# inkubator.net
KiCad netlist of a schematic drawn in EAGLE
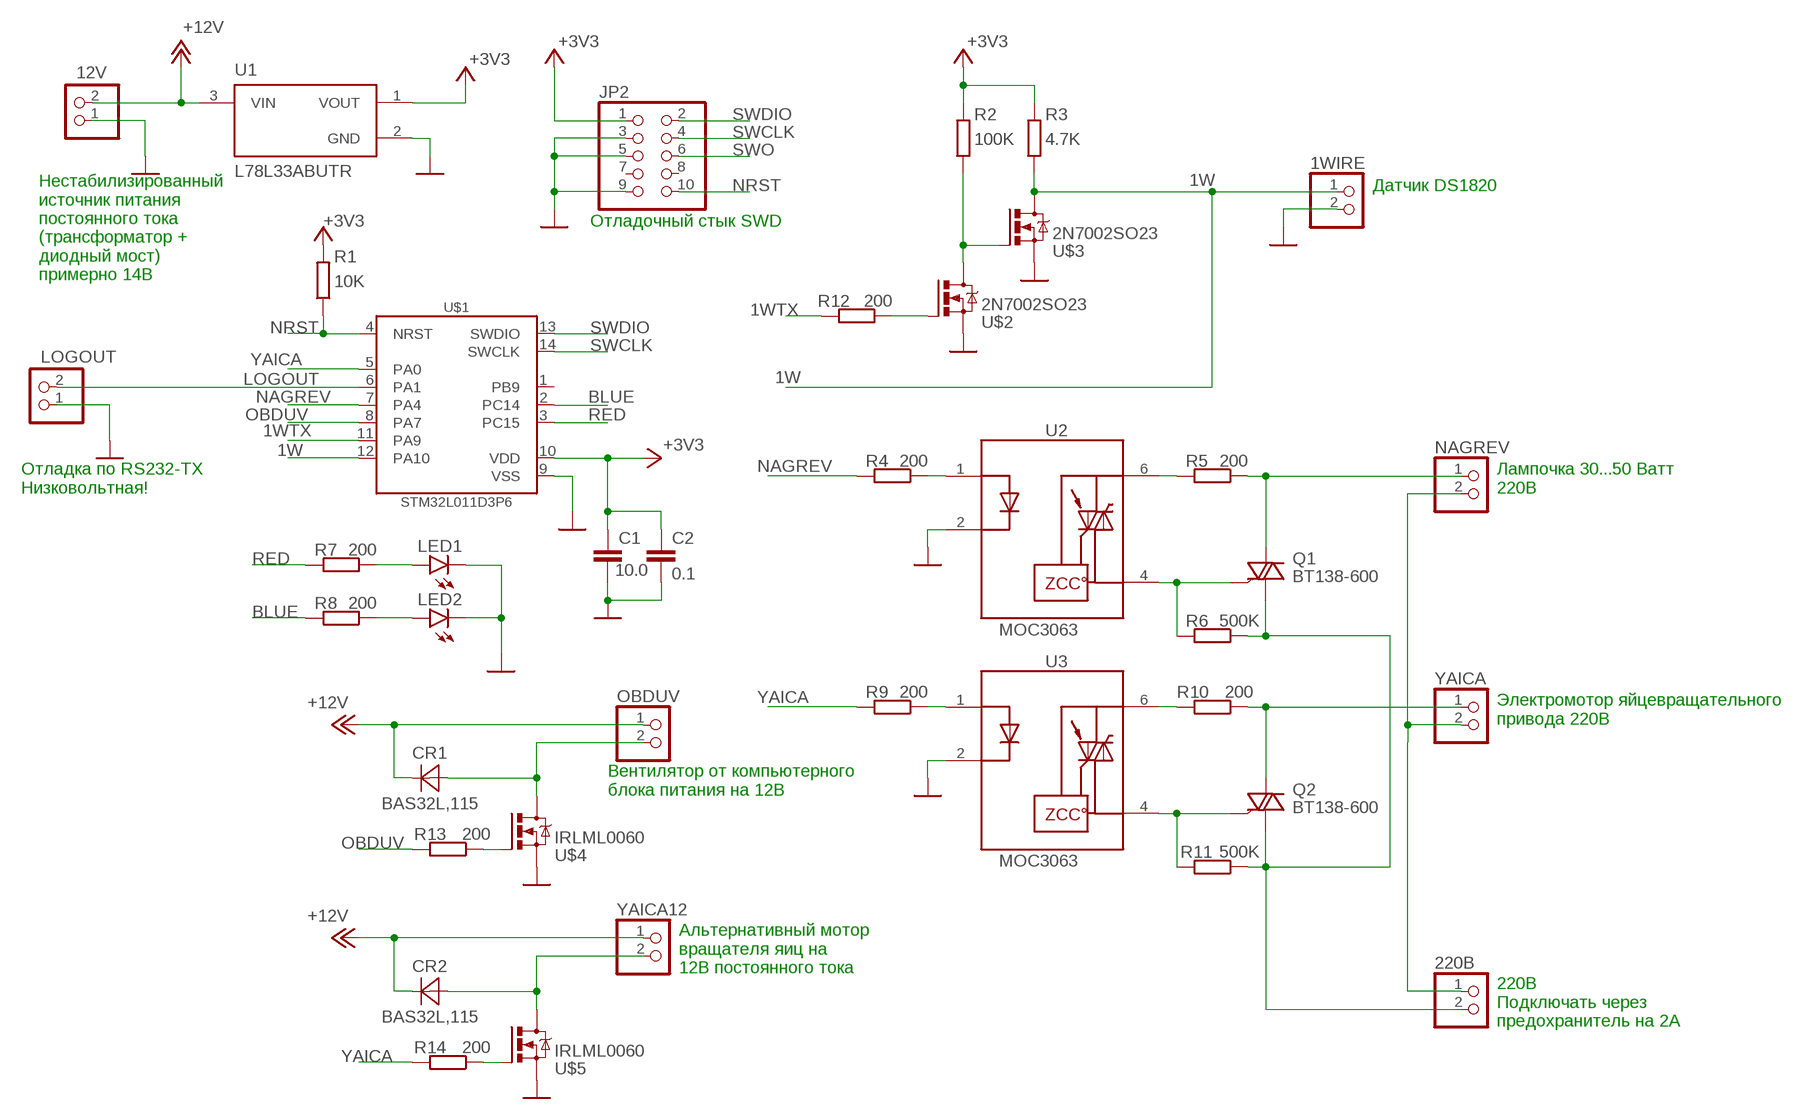
[diagram p0: schematic, sheet 1]

(export (version "E")
  (design (tool "Eeschema 10.0.6"))
  (components
    (comp (ref "1WIRE")
      (value "PINHD-1X2")
      (footprint "eagle-import:1X02")
      (libsource (lib "eagle-import") (part "PINHD-1X2"))
    )
    (comp (ref "12V")
      (value "PINHD-1X2")
      (footprint "eagle-import:1X02")
      (libsource (lib "eagle-import") (part "PINHD-1X2"))
    )
    (comp (ref "220В")
      (value "PINHD-1X2")
      (footprint "eagle-import:1X02")
      (libsource (lib "eagle-import") (part "PINHD-1X2"))
    )
    (comp (ref "C1")
      (value "10.0")
      (footprint "eagle-import:C1206")
      (libsource (lib "eagle-import") (part "C-EUC1206"))
    )
    (comp (ref "C2")
      (value "0.1")
      (footprint "eagle-import:C1206")
      (libsource (lib "eagle-import") (part "C-EUC1206"))
    )
    (comp (ref "CR1")
      (value "BAS32L,115")
      (footprint "eagle-import:SOD80C")
      (fields (field (name "MF") "Nexperia USA"))
      (libsource (lib "eagle-import") (part "BAS32L,115"))
    )
    (comp (ref "CR2")
      (value "BAS32L,115")
      (footprint "eagle-import:SOD80C")
      (fields (field (name "MF") "Nexperia USA"))
      (libsource (lib "eagle-import") (part "BAS32L,115"))
    )
    (comp (ref "JP2")
      (value "PINHD-2X5")
      (footprint "eagle-import:2X05")
      (libsource (lib "eagle-import") (part "PINHD-2X5"))
    )
    (comp (ref "LED1")
      (value "LED10MM")
      (footprint "eagle-import:LED10MM")
      (libsource (lib "eagle-import") (part "LED10MM"))
    )
    (comp (ref "LED2")
      (value "LED10MM")
      (footprint "eagle-import:LED10MM")
      (libsource (lib "eagle-import") (part "LED10MM"))
    )
    (comp (ref "LOGOUT")
      (value "PINHD-1X2")
      (footprint "eagle-import:1X02")
      (libsource (lib "eagle-import") (part "PINHD-1X2"))
    )
    (comp (ref "NAGREV")
      (value "PINHD-1X2")
      (footprint "eagle-import:1X02")
      (libsource (lib "eagle-import") (part "PINHD-1X2"))
    )
    (comp (ref "OBDUV")
      (value "PINHD-1X2")
      (footprint "eagle-import:1X02")
      (libsource (lib "eagle-import") (part "PINHD-1X2"))
    )
    (comp (ref "Q1")
      (value "BT138-600")
      (footprint "eagle-import:DPAK")
      (fields (field (name "MF") "STMicroelectronics") (field (name "MP") "T810-600B-TR"))
      (libsource (lib "eagle-import") (part "T810-600B-TR"))
    )
    (comp (ref "Q2")
      (value "BT138-600")
      (footprint "eagle-import:DPAK")
      (fields (field (name "MF") "STMicroelectronics") (field (name "MP") "T810-600B-TR"))
      (libsource (lib "eagle-import") (part "T810-600B-TR"))
    )
    (comp (ref "R1")
      (value "10K")
      (footprint "eagle-import:R0603")
      (libsource (lib "eagle-import") (part "R-EU_R0603"))
    )
    (comp (ref "R2")
      (value "100K")
      (footprint "eagle-import:R0603")
      (libsource (lib "eagle-import") (part "R-EU_R0603"))
    )
    (comp (ref "R3")
      (value "4.7K")
      (footprint "eagle-import:R0603")
      (libsource (lib "eagle-import") (part "R-EU_R0603"))
    )
    (comp (ref "R4")
      (value "200")
      (footprint "eagle-import:R0603")
      (libsource (lib "eagle-import") (part "R-EU_R0603"))
    )
    (comp (ref "R5")
      (value "200")
      (footprint "eagle-import:R1206")
      (libsource (lib "eagle-import") (part "R-EU_R1206"))
    )
    (comp (ref "R6")
      (value "500K")
      (footprint "eagle-import:R1206")
      (libsource (lib "eagle-import") (part "R-EU_R1206"))
    )
    (comp (ref "R7")
      (value "200")
      (footprint "eagle-import:R0603")
      (libsource (lib "eagle-import") (part "R-EU_R0603"))
    )
    (comp (ref "R8")
      (value "200")
      (footprint "eagle-import:R0603")
      (libsource (lib "eagle-import") (part "R-EU_R0603"))
    )
    (comp (ref "R9")
      (value "200")
      (footprint "eagle-import:R0603")
      (libsource (lib "eagle-import") (part "R-EU_R0603"))
    )
    (comp (ref "R10")
      (value "200")
      (footprint "eagle-import:R1206")
      (libsource (lib "eagle-import") (part "R-EU_R1206"))
    )
    (comp (ref "R11")
      (value "500K")
      (footprint "eagle-import:R1206")
      (libsource (lib "eagle-import") (part "R-EU_R1206"))
    )
    (comp (ref "R12")
      (value "200")
      (footprint "eagle-import:R0603")
      (libsource (lib "eagle-import") (part "R-EU_R0603"))
    )
    (comp (ref "R13")
      (value "200")
      (footprint "eagle-import:R0603")
      (libsource (lib "eagle-import") (part "R-EU_R0603"))
    )
    (comp (ref "R14")
      (value "200")
      (footprint "eagle-import:R0603")
      (libsource (lib "eagle-import") (part "R-EU_R0603"))
    )
    (comp (ref "U$1")
      (value "STM32L011D3P6")
      (footprint "eagle-import:SOP65P640X120-14N")
      (libsource (lib "eagle-import") (part "STM32L011D3P6"))
    )
    (comp (ref "U$2")
      (value "2N7002SO23")
      (footprint "eagle-import:SOT23")
      (libsource (lib "eagle-import") (part "2N7002SO23"))
    )
    (comp (ref "U$3")
      (value "2N7002SO23")
      (footprint "eagle-import:SOT23")
      (libsource (lib "eagle-import") (part "2N7002SO23"))
    )
    (comp (ref "U$4")
      (value "IRLML0060")
      (footprint "eagle-import:SOT23")
      (libsource (lib "eagle-import") (part "2N7002SO23"))
    )
    (comp (ref "U$5")
      (value "IRLML0060")
      (footprint "eagle-import:SOT23")
      (libsource (lib "eagle-import") (part "2N7002SO23"))
    )
    (comp (ref "U1")
      (value "L78L33ABUTR")
      (footprint "eagle-import:VREG_L78L12ABUTR")
      (fields (field (name "MF") "STMicroelectronics") (field (name "MP") "L78L12ABUTR"))
      (libsource (lib "eagle-import") (part "L78L12ABUTR"))
    )
    (comp (ref "U2")
      (value "MOC3063")
      (footprint "eagle-import:SOIC254P1030X460-6N")
      (fields (field (name "MF") "Vishay Semiconductor") (field (name "MP") "VO3062-X017T"))
      (libsource (lib "eagle-import") (part "VO3062-X017T"))
    )
    (comp (ref "U3")
      (value "MOC3063")
      (footprint "eagle-import:SOIC254P1030X460-6N")
      (fields (field (name "MF") "Vishay Semiconductor") (field (name "MP") "VO3062-X017T"))
      (libsource (lib "eagle-import") (part "VO3062-X017T"))
    )
    (comp (ref "YAICA")
      (value "PINHD-1X2")
      (footprint "eagle-import:1X02")
      (libsource (lib "eagle-import") (part "PINHD-1X2"))
    )
    (comp (ref "YAICA12")
      (value "PINHD-1X2")
      (footprint "eagle-import:1X02")
      (libsource (lib "eagle-import") (part "PINHD-1X2"))
    )
  )
  (nets
    (net (code "1") (name "+3V3") (class "Default")
      (node (ref "C1") (pin "1") (pinfunction "1_1") (pintype "passive"))
      (node (ref "C2") (pin "1") (pinfunction "1_1") (pintype "passive"))
      (node (ref "JP2") (pin "1") (pinfunction "1_1") (pintype "passive"))
      (node (ref "R1") (pin "2") (pinfunction "2_2") (pintype "passive"))
      (node (ref "R2") (pin "2") (pinfunction "2_2") (pintype "passive"))
      (node (ref "R3") (pin "2") (pinfunction "2_2") (pintype "passive"))
      (node (ref "U$1") (pin "10") (pinfunction "VDD_10") (pintype "power_in"))
      (node (ref "U1") (pin "1") (pinfunction "VOUT_1") (pintype "output"))
    )
    (net (code "2") (name "+12V") (class "Default")
      (node (ref "12V") (pin "2") (pinfunction "2_2") (pintype "passive"))
      (node (ref "CR1") (pin "1") (pinfunction "CATHODE_1") (pintype "passive"))
      (node (ref "CR2") (pin "1") (pinfunction "CATHODE_1") (pintype "passive"))
      (node (ref "OBDUV") (pin "1") (pinfunction "1_1") (pintype "passive"))
      (node (ref "U1") (pin "3") (pinfunction "VIN_3") (pintype "input"))
      (node (ref "YAICA12") (pin "1") (pinfunction "1_1") (pintype "passive"))
    )
    (net (code "3") (name "/1W") (class "Default")
      (node (ref "1WIRE") (pin "1") (pinfunction "1_1") (pintype "passive"))
      (node (ref "R3") (pin "1") (pinfunction "1_1") (pintype "passive"))
      (node (ref "U$1") (pin "12") (pinfunction "PA10_12") (pintype "bidirectional"))
      (node (ref "U$3") (pin "3") (pinfunction "D_3") (pintype "bidirectional"))
    )
    (net (code "4") (name "/1WTX") (class "Default")
      (node (ref "R12") (pin "2") (pinfunction "2_2") (pintype "passive"))
      (node (ref "U$1") (pin "11") (pinfunction "PA9_11") (pintype "bidirectional"))
    )
    (net (code "5") (name "/BLUE") (class "Default")
      (node (ref "R8") (pin "2") (pinfunction "2_2") (pintype "passive"))
      (node (ref "U$1") (pin "2") (pinfunction "PC14_2") (pintype "bidirectional"))
    )
    (net (code "6") (name "/LOGOUT") (class "Default")
      (node (ref "LOGOUT") (pin "2") (pinfunction "2_2") (pintype "passive"))
      (node (ref "U$1") (pin "6") (pinfunction "PA1_6") (pintype "bidirectional"))
    )
    (net (code "7") (name "/NAGREV") (class "Default")
      (node (ref "R4") (pin "2") (pinfunction "2_2") (pintype "passive"))
      (node (ref "U$1") (pin "7") (pinfunction "PA4_7") (pintype "bidirectional"))
    )
    (net (code "8") (name "/NRST") (class "Default")
      (node (ref "JP2") (pin "10") (pinfunction "10_10") (pintype "passive"))
      (node (ref "R1") (pin "1") (pinfunction "1_1") (pintype "passive"))
      (node (ref "U$1") (pin "4") (pinfunction "NRST_4") (pintype "input"))
    )
    (net (code "9") (name "/OBDUV") (class "Default")
      (node (ref "R13") (pin "2") (pinfunction "2_2") (pintype "passive"))
      (node (ref "U$1") (pin "8") (pinfunction "PA7_8") (pintype "bidirectional"))
    )
    (net (code "10") (name "/RED") (class "Default")
      (node (ref "R7") (pin "2") (pinfunction "2_2") (pintype "passive"))
      (node (ref "U$1") (pin "3") (pinfunction "PC15_3") (pintype "bidirectional"))
    )
    (net (code "11") (name "/SWCLK") (class "Default")
      (node (ref "JP2") (pin "4") (pinfunction "4_4") (pintype "passive"))
      (node (ref "U$1") (pin "14") (pinfunction "SWCLK_14") (pintype "bidirectional"))
    )
    (net (code "12") (name "/SWDIO") (class "Default")
      (node (ref "JP2") (pin "2") (pinfunction "2_2") (pintype "passive"))
      (node (ref "U$1") (pin "13") (pinfunction "SWDIO_13") (pintype "bidirectional"))
    )
    (net (code "13") (name "/SWO") (class "Default")
      (node (ref "JP2") (pin "6") (pinfunction "6_6") (pintype "passive"))
    )
    (net (code "14") (name "/YAICA") (class "Default")
      (node (ref "R14") (pin "2") (pinfunction "2_2") (pintype "passive"))
      (node (ref "R9") (pin "2") (pinfunction "2_2") (pintype "passive"))
      (node (ref "U$1") (pin "5") (pinfunction "PA0_5") (pintype "bidirectional"))
    )
    (net (code "15") (name "GND") (class "Default")
      (node (ref "12V") (pin "1") (pinfunction "1_1") (pintype "passive"))
      (node (ref "1WIRE") (pin "2") (pinfunction "2_2") (pintype "passive"))
      (node (ref "C1") (pin "2") (pinfunction "2_2") (pintype "passive"))
      (node (ref "C2") (pin "2") (pinfunction "2_2") (pintype "passive"))
      (node (ref "JP2") (pin "3") (pinfunction "3_3") (pintype "passive"))
      (node (ref "JP2") (pin "5") (pinfunction "5_5") (pintype "passive"))
      (node (ref "JP2") (pin "9") (pinfunction "9_9") (pintype "passive"))
      (node (ref "LED1") (pin "K") (pinfunction "C_K") (pintype "passive"))
      (node (ref "LED2") (pin "K") (pinfunction "C_K") (pintype "passive"))
      (node (ref "LOGOUT") (pin "1") (pinfunction "1_1") (pintype "passive"))
      (node (ref "U$1") (pin "9") (pinfunction "VSS_9") (pintype "power_in"))
      (node (ref "U$2") (pin "2") (pinfunction "S_2") (pintype "bidirectional"))
      (node (ref "U$3") (pin "2") (pinfunction "S_2") (pintype "bidirectional"))
      (node (ref "U$4") (pin "2") (pinfunction "S_2") (pintype "bidirectional"))
      (node (ref "U$5") (pin "2") (pinfunction "S_2") (pintype "bidirectional"))
      (node (ref "U1") (pin "2") (pinfunction "GND_2") (pintype "power_in"))
      (node (ref "U2") (pin "2") (pinfunction "C_2") (pintype "passive"))
      (node (ref "U3") (pin "2") (pinfunction "C_2") (pintype "passive"))
    )
    (net (code "16") (name "Net-(220В-Pad1)") (class "Default")
      (node (ref "220В") (pin "1") (pinfunction "1_1") (pintype "passive"))
      (node (ref "NAGREV") (pin "2") (pinfunction "2_2") (pintype "passive"))
      (node (ref "YAICA") (pin "2") (pinfunction "2_2") (pintype "passive"))
    )
    (net (code "17") (name "Net-(CR1-ANODE)") (class "Default")
      (node (ref "CR1") (pin "2") (pinfunction "ANODE_2") (pintype "passive"))
      (node (ref "OBDUV") (pin "2") (pinfunction "2_2") (pintype "passive"))
      (node (ref "U$4") (pin "3") (pinfunction "D_3") (pintype "bidirectional"))
    )
    (net (code "18") (name "Net-(CR2-ANODE)") (class "Default")
      (node (ref "CR2") (pin "2") (pinfunction "ANODE_2") (pintype "passive"))
      (node (ref "U$5") (pin "3") (pinfunction "D_3") (pintype "bidirectional"))
      (node (ref "YAICA12") (pin "2") (pinfunction "2_2") (pintype "passive"))
    )
    (net (code "19") (name "Net-(LED1-PadA)") (class "Default")
      (node (ref "LED1") (pin "A") (pinfunction "A_A") (pintype "passive"))
      (node (ref "R7") (pin "1") (pinfunction "1_1") (pintype "passive"))
    )
    (net (code "20") (name "Net-(LED2-PadA)") (class "Default")
      (node (ref "LED2") (pin "A") (pinfunction "A_A") (pintype "passive"))
      (node (ref "R8") (pin "1") (pinfunction "1_1") (pintype "passive"))
    )
    (net (code "21") (name "Net-(Q1-A1)") (class "Default")
      (node (ref "220В") (pin "2") (pinfunction "2_2") (pintype "passive"))
      (node (ref "Q1") (pin "1") (pinfunction "A1_1") (pintype "passive"))
      (node (ref "Q2") (pin "1") (pinfunction "A1_1") (pintype "passive"))
      (node (ref "R11") (pin "1") (pinfunction "1_1") (pintype "passive"))
      (node (ref "R6") (pin "1") (pinfunction "1_1") (pintype "passive"))
    )
    (net (code "22") (name "Net-(Q1-A2)") (class "Default")
      (node (ref "NAGREV") (pin "1") (pinfunction "1_1") (pintype "passive"))
      (node (ref "Q1") (pin "2") (pinfunction "A2_2") (pintype "passive"))
      (node (ref "R5") (pin "1") (pinfunction "1_1") (pintype "passive"))
    )
    (net (code "23") (name "Net-(Q1-G)") (class "Default")
      (node (ref "Q1") (pin "3") (pinfunction "G_3") (pintype "passive"))
      (node (ref "R6") (pin "2") (pinfunction "2_2") (pintype "passive"))
      (node (ref "U2") (pin "4") (pinfunction "MT1_4") (pintype "passive"))
    )
    (net (code "24") (name "Net-(Q2-A2)") (class "Default")
      (node (ref "Q2") (pin "2") (pinfunction "A2_2") (pintype "passive"))
      (node (ref "R10") (pin "1") (pinfunction "1_1") (pintype "passive"))
      (node (ref "YAICA") (pin "1") (pinfunction "1_1") (pintype "passive"))
    )
    (net (code "25") (name "Net-(Q2-G)") (class "Default")
      (node (ref "Q2") (pin "3") (pinfunction "G_3") (pintype "passive"))
      (node (ref "R11") (pin "2") (pinfunction "2_2") (pintype "passive"))
      (node (ref "U3") (pin "4") (pinfunction "MT1_4") (pintype "passive"))
    )
    (net (code "26") (name "Net-(U$2-D)") (class "Default")
      (node (ref "R2") (pin "1") (pinfunction "1_1") (pintype "passive"))
      (node (ref "U$2") (pin "3") (pinfunction "D_3") (pintype "bidirectional"))
      (node (ref "U$3") (pin "1") (pinfunction "G_1") (pintype "bidirectional"))
    )
    (net (code "27") (name "Net-(U$2-G)") (class "Default")
      (node (ref "R12") (pin "1") (pinfunction "1_1") (pintype "passive"))
      (node (ref "U$2") (pin "1") (pinfunction "G_1") (pintype "bidirectional"))
    )
    (net (code "28") (name "Net-(U$4-G)") (class "Default")
      (node (ref "R13") (pin "1") (pinfunction "1_1") (pintype "passive"))
      (node (ref "U$4") (pin "1") (pinfunction "G_1") (pintype "bidirectional"))
    )
    (net (code "29") (name "Net-(U$5-G)") (class "Default")
      (node (ref "R14") (pin "1") (pinfunction "1_1") (pintype "passive"))
      (node (ref "U$5") (pin "1") (pinfunction "G_1") (pintype "bidirectional"))
    )
    (net (code "30") (name "Net-(U2-A)") (class "Default")
      (node (ref "R4") (pin "1") (pinfunction "1_1") (pintype "passive"))
      (node (ref "U2") (pin "1") (pinfunction "A_1") (pintype "passive"))
    )
    (net (code "31") (name "Net-(U2-MT2)") (class "Default")
      (node (ref "R5") (pin "2") (pinfunction "2_2") (pintype "passive"))
      (node (ref "U2") (pin "6") (pinfunction "MT2_6") (pintype "passive"))
    )
    (net (code "32") (name "Net-(U3-A)") (class "Default")
      (node (ref "R9") (pin "1") (pinfunction "1_1") (pintype "passive"))
      (node (ref "U3") (pin "1") (pinfunction "A_1") (pintype "passive"))
    )
    (net (code "33") (name "Net-(U3-MT2)") (class "Default")
      (node (ref "R10") (pin "2") (pinfunction "2_2") (pintype "passive"))
      (node (ref "U3") (pin "6") (pinfunction "MT2_6") (pintype "passive"))
    )
    (net (code "34") (name "unconnected-(JP2-Pad7)") (class "Default")
      (node (ref "JP2") (pin "7") (pinfunction "7_7") (pintype "passive"))
    )
    (net (code "35") (name "unconnected-(JP2-Pad8)") (class "Default")
      (node (ref "JP2") (pin "8") (pinfunction "8_8") (pintype "passive"))
    )
    (net (code "36") (name "unconnected-(U$1-PB9-Pad1)") (class "Default")
      (node (ref "U$1") (pin "1") (pinfunction "PB9_1") (pintype "bidirectional"))
    )
  )
)
